# COMMUNICATION.net
KiCad netlist of a schematic drawn in Altium Designer
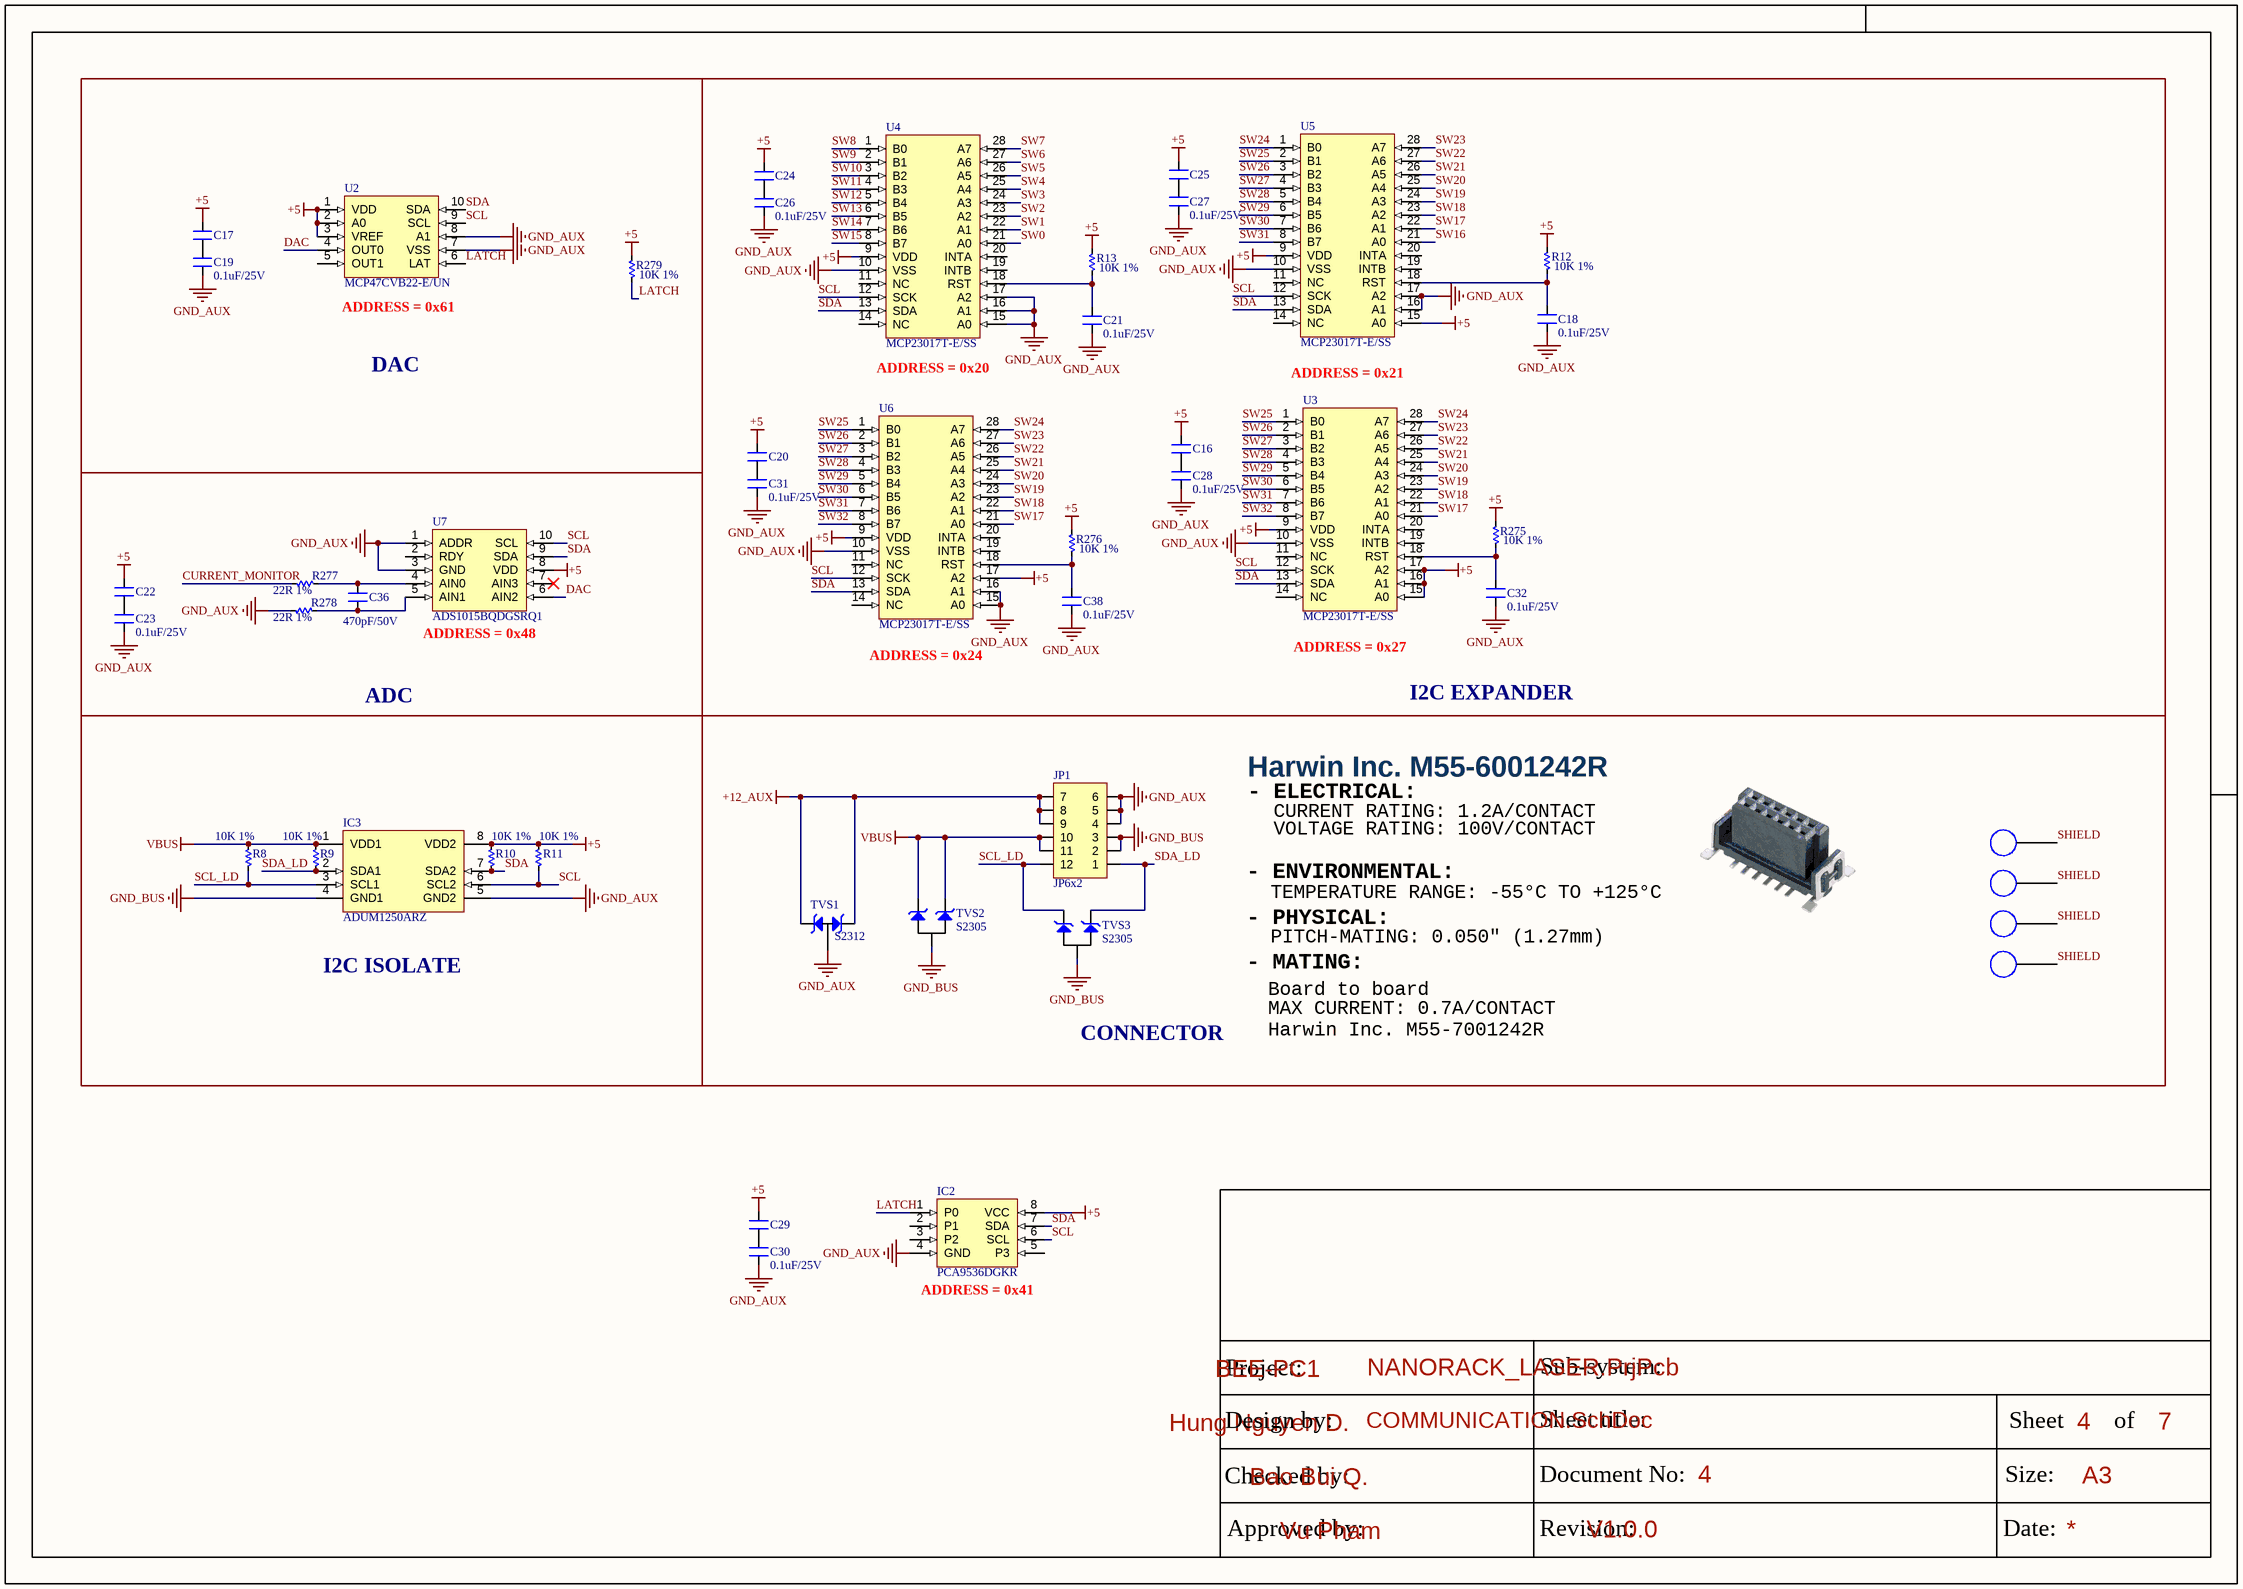
[diagram p0: COMMUNICATION.SchDoc]

(export (version "E")
  (design (tool "Eeschema 10.0.6"))
  (components
    (comp (ref "C16")
      (value "0.1uF/25V")
      (footprint "SM-0603")
      (description "0603")
      (libsource (lib "Capacitors") (part "CM"))
    )
    (comp (ref "C17")
      (value "0.1uF/25V")
      (footprint "SM-0603")
      (description "0603")
      (libsource (lib "Capacitors") (part "CM"))
    )
    (comp (ref "C18")
      (value "0.1uF/25V")
      (footprint "SM-0603")
      (description "0603")
      (libsource (lib "Capacitors") (part "CM"))
    )
    (comp (ref "C19")
      (value "0.1uF/25V")
      (footprint "SM-0603")
      (description "0603")
      (libsource (lib "Capacitors") (part "CM"))
    )
    (comp (ref "C20")
      (value "0.1uF/25V")
      (footprint "SM-0603")
      (description "0603")
      (libsource (lib "Capacitors") (part "CM"))
    )
    (comp (ref "C21")
      (value "0.1uF/25V")
      (footprint "SM-0603")
      (description "0603")
      (libsource (lib "Capacitors") (part "CM"))
    )
    (comp (ref "C22")
      (value "0.1uF/25V")
      (footprint "SM-0603")
      (description "0603")
      (libsource (lib "Capacitors") (part "CM"))
    )
    (comp (ref "C23")
      (value "0.1uF/25V")
      (footprint "SM-0603")
      (description "0603")
      (libsource (lib "Capacitors") (part "CM"))
    )
    (comp (ref "C24")
      (value "0.1uF/25V")
      (footprint "SM-0603")
      (description "0603")
      (libsource (lib "Capacitors") (part "CM"))
    )
    (comp (ref "C25")
      (value "0.1uF/25V")
      (footprint "SM-0603")
      (description "0603")
      (libsource (lib "Capacitors") (part "CM"))
    )
    (comp (ref "C26")
      (value "0.1uF/25V")
      (footprint "SM-0603")
      (description "0603")
      (libsource (lib "Capacitors") (part "CM"))
    )
    (comp (ref "C27")
      (value "0.1uF/25V")
      (footprint "SM-0603")
      (description "0603")
      (libsource (lib "Capacitors") (part "CM"))
    )
    (comp (ref "C28")
      (value "0.1uF/25V")
      (footprint "SM-0603")
      (description "0603")
      (libsource (lib "Capacitors") (part "CM"))
    )
    (comp (ref "C29")
      (value "0.1uF/25V")
      (footprint "SM-0603")
      (description "0603")
      (libsource (lib "Capacitors") (part "CM"))
    )
    (comp (ref "C30")
      (value "0.1uF/25V")
      (footprint "SM-0603")
      (description "0603")
      (libsource (lib "Capacitors") (part "CM"))
    )
    (comp (ref "C31")
      (value "0.1uF/25V")
      (footprint "SM-0603")
      (description "0603")
      (libsource (lib "Capacitors") (part "CM"))
    )
    (comp (ref "C32")
      (value "0.1uF/25V")
      (footprint "SM-0603")
      (description "0603")
      (libsource (lib "Capacitors") (part "CM"))
    )
    (comp (ref "C36")
      (value "470pF/50V")
      (footprint "SM-0603")
      (description "0603")
      (libsource (lib "Capacitors") (part "CM"))
    )
    (comp (ref "C38")
      (value "0.1uF/25V")
      (footprint "SM-0603")
      (description "0603")
      (libsource (lib "Capacitors") (part "CM"))
    )
    (comp (ref "H1") (value "M3") (footprint "M3") (libsource (lib "Library") (part "M3")))
    (comp (ref "H2") (value "M3") (footprint "M3") (libsource (lib "Library") (part "M3")))
    (comp (ref "H3") (value "M3") (footprint "M3") (libsource (lib "Library") (part "M3")))
    (comp (ref "H4") (value "M3") (footprint "M3") (libsource (lib "Library") (part "M3")))
    (comp (ref "IC2") (value "PCA9536DGKR") (footprint "TSSOP8") (libsource (lib "Library") (part "PCA9536")))
    (comp (ref "IC3") (value "ADUM1250ARZ") (footprint "SO8") (libsource (lib "Library") (part "ADUM1250")))
    (comp (ref "JP1")
      (value "JP6x2")
      (footprint "M55-6001242R")
      (description "WR-PHD 2.54 mm Dual Socket Header")
      (fields
        (field (name "MANUFACTURER") "Würth Elektronik eiSos GmbH")
        (field (name "PARTNO") "61301221821")
        (field (name "CREATED BY") "Karrer Zheng")
      )
      (libsource (lib "Library") (part "JP6x2"))
    )
    (comp (ref "R8")
      (value "10K 1%")
      (footprint "RES-SMD-0603")
      (description "0603")
      (fields
        (field (name "MANUFACTURER") "Generic Components")
        (field (name "PUBLISHER") "Altium Hobart Technology Centre")
      )
      (libsource (lib "Library") (part "Res-SMD"))
    )
    (comp (ref "R9")
      (value "10K 1%")
      (footprint "RES-SMD-0603")
      (description "0603")
      (fields
        (field (name "MANUFACTURER") "Generic Components")
        (field (name "PUBLISHER") "Altium Hobart Technology Centre")
      )
      (libsource (lib "Library") (part "Res-SMD"))
    )
    (comp (ref "R10")
      (value "10K 1%")
      (footprint "RES-SMD-0603")
      (description "0603")
      (fields
        (field (name "MANUFACTURER") "Generic Components")
        (field (name "PUBLISHER") "Altium Hobart Technology Centre")
      )
      (libsource (lib "Library") (part "Res-SMD"))
    )
    (comp (ref "R11")
      (value "10K 1%")
      (footprint "RES-SMD-0603")
      (description "0603")
      (fields
        (field (name "MANUFACTURER") "Generic Components")
        (field (name "PUBLISHER") "Altium Hobart Technology Centre")
      )
      (libsource (lib "Library") (part "Res-SMD"))
    )
    (comp (ref "R12")
      (value "10K 1%")
      (footprint "RES-SMD-0603")
      (description "0603")
      (fields
        (field (name "MANUFACTURER") "Generic Components")
        (field (name "PUBLISHER") "Altium Hobart Technology Centre")
      )
      (libsource (lib "Library") (part "Res-SMD"))
    )
    (comp (ref "R13")
      (value "10K 1%")
      (footprint "RES-SMD-0603")
      (description "0603")
      (fields
        (field (name "MANUFACTURER") "Generic Components")
        (field (name "PUBLISHER") "Altium Hobart Technology Centre")
      )
      (libsource (lib "Library") (part "Res-SMD"))
    )
    (comp (ref "R275")
      (value "10K 1%")
      (footprint "RES-SMD-0603")
      (description "0603")
      (fields
        (field (name "MANUFACTURER") "Generic Components")
        (field (name "PUBLISHER") "Altium Hobart Technology Centre")
      )
      (libsource (lib "Library") (part "Res-SMD"))
    )
    (comp (ref "R276")
      (value "10K 1%")
      (footprint "RES-SMD-0603")
      (description "0603")
      (fields
        (field (name "MANUFACTURER") "Generic Components")
        (field (name "PUBLISHER") "Altium Hobart Technology Centre")
      )
      (libsource (lib "Library") (part "Res-SMD"))
    )
    (comp (ref "R277")
      (value "22R 1%")
      (footprint "RES-SMD-0603")
      (description "0603")
      (fields
        (field (name "MANUFACTURER") "Generic Components")
        (field (name "PUBLISHER") "Altium Hobart Technology Centre")
      )
      (libsource (lib "Library") (part "Res-SMD"))
    )
    (comp (ref "R278")
      (value "22R 1%")
      (footprint "RES-SMD-0603")
      (description "0603")
      (fields
        (field (name "MANUFACTURER") "Generic Components")
        (field (name "PUBLISHER") "Altium Hobart Technology Centre")
      )
      (libsource (lib "Library") (part "Res-SMD"))
    )
    (comp (ref "R279")
      (value "10K 1%")
      (footprint "RES-SMD-0603")
      (description "0603")
      (fields
        (field (name "MANUFACTURER") "Generic Components")
        (field (name "PUBLISHER") "Altium Hobart Technology Centre")
      )
      (libsource (lib "Library") (part "Res-SMD"))
    )
    (comp (ref "TVS1")
      (value "S2312")
      (footprint "SOT23-123")
      (description "TVS DIODE 12VWM 19VC SOT23, P/N:  S2312")
      (libsource (lib "Library") (part "S2315"))
    )
    (comp (ref "TVS2")
      (value "S2305")
      (footprint "SOT23-123")
      (description "TVS DIODE 5VWM 10.8VC SOT23, P/N:  \r\nS2305")
      (libsource (lib "Library") (part "S2303"))
    )
    (comp (ref "TVS3")
      (value "S2305")
      (footprint "SOT23-123")
      (description "TVS DIODE 5VWM 10.8VC SOT23, P/N:  \r\nS2305")
      (libsource (lib "Library") (part "S2303"))
    )
    (comp (ref "U2")
      (value "MCP47CVB22-E/UN")
      (footprint "MSOP10")
      (libsource (lib "Library") (part "MCP47CVB22"))
    )
    (comp (ref "U3")
      (value "MCP23017T-E/SS")
      (footprint "SSOP28")
      (libsource (lib "Library") (part "MCP23017"))
    )
    (comp (ref "U4")
      (value "MCP23017T-E/SS")
      (footprint "SSOP28")
      (libsource (lib "Library") (part "MCP23017"))
    )
    (comp (ref "U5")
      (value "MCP23017T-E/SS")
      (footprint "SSOP28")
      (libsource (lib "Library") (part "MCP23017"))
    )
    (comp (ref "U6")
      (value "MCP23017T-E/SS")
      (footprint "SSOP28")
      (libsource (lib "Library") (part "MCP23017"))
    )
    (comp (ref "U7")
      (value "ADS1015BQDGSRQ1")
      (footprint "VSSOP10")
      (libsource (lib "Library") (part "ADS1015"))
    )
  )
  (nets
    (net (code "1") (name "+5") (class "Default")
      (node (ref "C16") (pin "2") (pinfunction "2_2") (pintype "passive"))
      (node (ref "C17") (pin "2") (pinfunction "2_2") (pintype "passive"))
      (node (ref "C20") (pin "2") (pinfunction "2_2") (pintype "passive"))
      (node (ref "C22") (pin "2") (pinfunction "2_2") (pintype "passive"))
      (node (ref "C24") (pin "2") (pinfunction "2_2") (pintype "passive"))
      (node (ref "C25") (pin "2") (pinfunction "2_2") (pintype "passive"))
      (node (ref "C29") (pin "2") (pinfunction "2_2") (pintype "passive"))
      (node (ref "IC2") (pin "8") (pinfunction "VCC_8") (pintype "input"))
      (node (ref "IC3") (pin "8") (pinfunction "VDD2_8") (pintype "power_in"))
      (node (ref "R10") (pin "2") (pinfunction "2_2") (pintype "passive"))
      (node (ref "R11") (pin "2") (pinfunction "2_2") (pintype "passive"))
      (node (ref "R12") (pin "2") (pinfunction "2_2") (pintype "passive"))
      (node (ref "R13") (pin "2") (pinfunction "2_2") (pintype "passive"))
      (node (ref "R275") (pin "2") (pinfunction "2_2") (pintype "passive"))
      (node (ref "R276") (pin "2") (pinfunction "2_2") (pintype "passive"))
      (node (ref "R279") (pin "2") (pinfunction "2_2") (pintype "passive"))
      (node (ref "U2") (pin "1") (pinfunction "VDD_1") (pintype "input"))
      (node (ref "U2") (pin "2") (pinfunction "A0_2") (pintype "input"))
      (node (ref "U2") (pin "3") (pinfunction "VREF_3") (pintype "input"))
      (node (ref "U3") (pin "15") (pinfunction "A0_15") (pintype "input"))
      (node (ref "U3") (pin "16") (pinfunction "A1_16") (pintype "input"))
      (node (ref "U3") (pin "17") (pinfunction "A2_17") (pintype "input"))
      (node (ref "U3") (pin "9") (pinfunction "VDD_9") (pintype "input"))
      (node (ref "U4") (pin "9") (pinfunction "VDD_9") (pintype "input"))
      (node (ref "U5") (pin "15") (pinfunction "A0_15") (pintype "input"))
      (node (ref "U5") (pin "9") (pinfunction "VDD_9") (pintype "input"))
      (node (ref "U6") (pin "17") (pinfunction "A2_17") (pintype "input"))
      (node (ref "U6") (pin "9") (pinfunction "VDD_9") (pintype "input"))
      (node (ref "U7") (pin "8") (pinfunction "VDD_8") (pintype "input"))
    )
    (net (code "2") (name "+12_AUX") (class "Default")
      (node (ref "JP1") (pin "7") (pinfunction "7_7") (pintype "passive"))
      (node (ref "JP1") (pin "8") (pinfunction "8_8") (pintype "passive"))
      (node (ref "JP1") (pin "9") (pinfunction "9_9") (pintype "passive"))
      (node (ref "TVS1") (pin "1") (pintype "passive"))
      (node (ref "TVS1") (pin "3") (pintype "passive"))
    )
    (net (code "3") (name "/CURRENT_MONITOR") (class "Default")
      (node (ref "R277") (pin "2") (pinfunction "2_2") (pintype "passive"))
    )
    (net (code "4") (name "/DAC") (class "Default")
      (node (ref "U2") (pin "4") (pinfunction "OUT0_4") (pintype "input"))
      (node (ref "U7") (pin "6") (pinfunction "AIN2_6") (pintype "input"))
    )
    (net (code "5") (name "/LATCH") (class "Default")
      (node (ref "IC2") (pin "1") (pinfunction "P0_1") (pintype "input"))
      (node (ref "R279") (pin "1") (pinfunction "1_1") (pintype "passive"))
      (node (ref "U2") (pin "6") (pinfunction "LAT_6") (pintype "input"))
    )
    (net (code "6") (name "/SCL") (class "Default")
      (node (ref "IC2") (pin "6") (pinfunction "SCL_6") (pintype "input"))
      (node (ref "IC3") (pin "6") (pinfunction "SCL2_6") (pintype "input"))
      (node (ref "R11") (pin "1") (pinfunction "1_1") (pintype "passive"))
      (node (ref "U2") (pin "9") (pinfunction "SCL_9") (pintype "input"))
      (node (ref "U3") (pin "12") (pinfunction "SCK_12") (pintype "input"))
      (node (ref "U4") (pin "12") (pinfunction "SCK_12") (pintype "input"))
      (node (ref "U5") (pin "12") (pinfunction "SCK_12") (pintype "input"))
      (node (ref "U6") (pin "12") (pinfunction "SCK_12") (pintype "input"))
      (node (ref "U7") (pin "10") (pinfunction "SCL_10") (pintype "input"))
    )
    (net (code "7") (name "/SCL_LD") (class "Default")
      (node (ref "IC3") (pin "3") (pinfunction "SCL1_3") (pintype "input"))
      (node (ref "JP1") (pin "12") (pinfunction "12_12") (pintype "passive"))
      (node (ref "R8") (pin "1") (pinfunction "1_1") (pintype "passive"))
      (node (ref "TVS3") (pin "3") (pintype "passive"))
    )
    (net (code "8") (name "/SDA") (class "Default")
      (node (ref "IC2") (pin "7") (pinfunction "SDA_7") (pintype "input"))
      (node (ref "IC3") (pin "7") (pinfunction "SDA2_7") (pintype "input"))
      (node (ref "R10") (pin "1") (pinfunction "1_1") (pintype "passive"))
      (node (ref "U2") (pin "10") (pinfunction "SDA_10") (pintype "input"))
      (node (ref "U3") (pin "13") (pinfunction "SDA_13") (pintype "input"))
      (node (ref "U4") (pin "13") (pinfunction "SDA_13") (pintype "input"))
      (node (ref "U5") (pin "13") (pinfunction "SDA_13") (pintype "input"))
      (node (ref "U6") (pin "13") (pinfunction "SDA_13") (pintype "input"))
      (node (ref "U7") (pin "9") (pinfunction "SDA_9") (pintype "input"))
    )
    (net (code "9") (name "/SDA_LD") (class "Default")
      (node (ref "IC3") (pin "2") (pinfunction "SDA1_2") (pintype "input"))
      (node (ref "JP1") (pin "1") (pinfunction "1_1") (pintype "passive"))
      (node (ref "R9") (pin "1") (pinfunction "1_1") (pintype "passive"))
      (node (ref "TVS3") (pin "1") (pintype "passive"))
    )
    (net (code "10") (name "/SHIELD") (class "Default")
      (node (ref "H1") (pin "1") (pinfunction "76_1") (pintype "passive"))
      (node (ref "H2") (pin "1") (pinfunction "76_1") (pintype "passive"))
      (node (ref "H3") (pin "1") (pinfunction "76_1") (pintype "passive"))
      (node (ref "H4") (pin "1") (pinfunction "76_1") (pintype "passive"))
    )
    (net (code "11") (name "/SW0") (class "Default")
      (node (ref "U4") (pin "21") (pinfunction "A0_21") (pintype "input"))
    )
    (net (code "12") (name "/SW1") (class "Default")
      (node (ref "U4") (pin "22") (pinfunction "A1_22") (pintype "input"))
    )
    (net (code "13") (name "/SW2") (class "Default")
      (node (ref "U4") (pin "23") (pinfunction "A2_23") (pintype "input"))
    )
    (net (code "14") (name "/SW3") (class "Default")
      (node (ref "U4") (pin "24") (pinfunction "A3_24") (pintype "input"))
    )
    (net (code "15") (name "/SW4") (class "Default")
      (node (ref "U4") (pin "25") (pinfunction "A4_25") (pintype "input"))
    )
    (net (code "16") (name "/SW5") (class "Default")
      (node (ref "U4") (pin "26") (pinfunction "A5_26") (pintype "input"))
    )
    (net (code "17") (name "/SW6") (class "Default")
      (node (ref "U4") (pin "27") (pinfunction "A6_27") (pintype "input"))
    )
    (net (code "18") (name "/SW7") (class "Default")
      (node (ref "U4") (pin "28") (pinfunction "A7_28") (pintype "input"))
    )
    (net (code "19") (name "/SW8") (class "Default")
      (node (ref "U4") (pin "1") (pinfunction "B0_1") (pintype "input"))
    )
    (net (code "20") (name "/SW9") (class "Default")
      (node (ref "U4") (pin "2") (pinfunction "B1_2") (pintype "input"))
    )
    (net (code "21") (name "/SW10") (class "Default")
      (node (ref "U4") (pin "3") (pinfunction "B2_3") (pintype "input"))
    )
    (net (code "22") (name "/SW11") (class "Default")
      (node (ref "U4") (pin "4") (pinfunction "B3_4") (pintype "input"))
    )
    (net (code "23") (name "/SW12") (class "Default")
      (node (ref "U4") (pin "5") (pinfunction "B4_5") (pintype "input"))
    )
    (net (code "24") (name "/SW13") (class "Default")
      (node (ref "U4") (pin "6") (pinfunction "B5_6") (pintype "input"))
    )
    (net (code "25") (name "/SW14") (class "Default")
      (node (ref "U4") (pin "7") (pinfunction "B6_7") (pintype "input"))
    )
    (net (code "26") (name "/SW15") (class "Default")
      (node (ref "U4") (pin "8") (pinfunction "B7_8") (pintype "input"))
    )
    (net (code "27") (name "/SW16") (class "Default")
      (node (ref "U5") (pin "21") (pinfunction "A0_21") (pintype "input"))
    )
    (net (code "28") (name "/SW17") (class "Default")
      (node (ref "U3") (pin "21") (pinfunction "A0_21") (pintype "input"))
      (node (ref "U5") (pin "22") (pinfunction "A1_22") (pintype "input"))
      (node (ref "U6") (pin "21") (pinfunction "A0_21") (pintype "input"))
    )
    (net (code "29") (name "/SW18") (class "Default")
      (node (ref "U3") (pin "22") (pinfunction "A1_22") (pintype "input"))
      (node (ref "U5") (pin "23") (pinfunction "A2_23") (pintype "input"))
      (node (ref "U6") (pin "22") (pinfunction "A1_22") (pintype "input"))
    )
    (net (code "30") (name "/SW19") (class "Default")
      (node (ref "U3") (pin "23") (pinfunction "A2_23") (pintype "input"))
      (node (ref "U5") (pin "24") (pinfunction "A3_24") (pintype "input"))
      (node (ref "U6") (pin "23") (pinfunction "A2_23") (pintype "input"))
    )
    (net (code "31") (name "/SW20") (class "Default")
      (node (ref "U3") (pin "24") (pinfunction "A3_24") (pintype "input"))
      (node (ref "U5") (pin "25") (pinfunction "A4_25") (pintype "input"))
      (node (ref "U6") (pin "24") (pinfunction "A3_24") (pintype "input"))
    )
    (net (code "32") (name "/SW21") (class "Default")
      (node (ref "U3") (pin "25") (pinfunction "A4_25") (pintype "input"))
      (node (ref "U5") (pin "26") (pinfunction "A5_26") (pintype "input"))
      (node (ref "U6") (pin "25") (pinfunction "A4_25") (pintype "input"))
    )
    (net (code "33") (name "/SW22") (class "Default")
      (node (ref "U3") (pin "26") (pinfunction "A5_26") (pintype "input"))
      (node (ref "U5") (pin "27") (pinfunction "A6_27") (pintype "input"))
      (node (ref "U6") (pin "26") (pinfunction "A5_26") (pintype "input"))
    )
    (net (code "34") (name "/SW23") (class "Default")
      (node (ref "U3") (pin "27") (pinfunction "A6_27") (pintype "input"))
      (node (ref "U5") (pin "28") (pinfunction "A7_28") (pintype "input"))
      (node (ref "U6") (pin "27") (pinfunction "A6_27") (pintype "input"))
    )
    (net (code "35") (name "/SW24") (class "Default")
      (node (ref "U3") (pin "28") (pinfunction "A7_28") (pintype "input"))
      (node (ref "U5") (pin "1") (pinfunction "B0_1") (pintype "input"))
      (node (ref "U6") (pin "28") (pinfunction "A7_28") (pintype "input"))
    )
    (net (code "36") (name "/SW25") (class "Default")
      (node (ref "U3") (pin "1") (pinfunction "B0_1") (pintype "input"))
      (node (ref "U5") (pin "2") (pinfunction "B1_2") (pintype "input"))
      (node (ref "U6") (pin "1") (pinfunction "B0_1") (pintype "input"))
    )
    (net (code "37") (name "/SW26") (class "Default")
      (node (ref "U3") (pin "2") (pinfunction "B1_2") (pintype "input"))
      (node (ref "U5") (pin "3") (pinfunction "B2_3") (pintype "input"))
      (node (ref "U6") (pin "2") (pinfunction "B1_2") (pintype "input"))
    )
    (net (code "38") (name "/SW27") (class "Default")
      (node (ref "U3") (pin "3") (pinfunction "B2_3") (pintype "input"))
      (node (ref "U5") (pin "4") (pinfunction "B3_4") (pintype "input"))
      (node (ref "U6") (pin "3") (pinfunction "B2_3") (pintype "input"))
    )
    (net (code "39") (name "/SW28") (class "Default")
      (node (ref "U3") (pin "4") (pinfunction "B3_4") (pintype "input"))
      (node (ref "U5") (pin "5") (pinfunction "B4_5") (pintype "input"))
      (node (ref "U6") (pin "4") (pinfunction "B3_4") (pintype "input"))
    )
    (net (code "40") (name "/SW29") (class "Default")
      (node (ref "U3") (pin "5") (pinfunction "B4_5") (pintype "input"))
      (node (ref "U5") (pin "6") (pinfunction "B5_6") (pintype "input"))
      (node (ref "U6") (pin "5") (pinfunction "B4_5") (pintype "input"))
    )
    (net (code "41") (name "/SW30") (class "Default")
      (node (ref "U3") (pin "6") (pinfunction "B5_6") (pintype "input"))
      (node (ref "U5") (pin "7") (pinfunction "B6_7") (pintype "input"))
      (node (ref "U6") (pin "6") (pinfunction "B5_6") (pintype "input"))
    )
    (net (code "42") (name "/SW31") (class "Default")
      (node (ref "U3") (pin "7") (pinfunction "B6_7") (pintype "input"))
      (node (ref "U5") (pin "8") (pinfunction "B7_8") (pintype "input"))
      (node (ref "U6") (pin "7") (pinfunction "B6_7") (pintype "input"))
    )
    (net (code "43") (name "/SW32") (class "Default")
      (node (ref "U3") (pin "8") (pinfunction "B7_8") (pintype "input"))
      (node (ref "U6") (pin "8") (pinfunction "B7_8") (pintype "input"))
    )
    (net (code "44") (name "GND_AUX") (class "Default")
      (node (ref "C18") (pin "1") (pinfunction "1_1") (pintype "passive"))
      (node (ref "C19") (pin "1") (pinfunction "1_1") (pintype "passive"))
      (node (ref "C21") (pin "1") (pinfunction "1_1") (pintype "passive"))
      (node (ref "C23") (pin "1") (pinfunction "1_1") (pintype "passive"))
      (node (ref "C26") (pin "1") (pinfunction "1_1") (pintype "passive"))
      (node (ref "C27") (pin "1") (pinfunction "1_1") (pintype "passive"))
      (node (ref "C28") (pin "1") (pinfunction "1_1") (pintype "passive"))
      (node (ref "C30") (pin "1") (pinfunction "1_1") (pintype "passive"))
      (node (ref "C31") (pin "1") (pinfunction "1_1") (pintype "passive"))
      (node (ref "C32") (pin "1") (pinfunction "1_1") (pintype "passive"))
      (node (ref "C38") (pin "1") (pinfunction "1_1") (pintype "passive"))
      (node (ref "IC2") (pin "4") (pinfunction "GND_4") (pintype "input"))
      (node (ref "IC3") (pin "5") (pinfunction "GND2_5") (pintype "power_in"))
      (node (ref "JP1") (pin "4") (pinfunction "4_4") (pintype "passive"))
      (node (ref "JP1") (pin "5") (pinfunction "5_5") (pintype "passive"))
      (node (ref "JP1") (pin "6") (pinfunction "6_6") (pintype "passive"))
      (node (ref "R278") (pin "2") (pinfunction "2_2") (pintype "passive"))
      (node (ref "TVS1") (pin "2") (pintype "passive"))
      (node (ref "U2") (pin "7") (pinfunction "VSS_7") (pintype "input"))
      (node (ref "U2") (pin "8") (pinfunction "A1_8") (pintype "input"))
      (node (ref "U3") (pin "10") (pinfunction "VSS_10") (pintype "input"))
      (node (ref "U4") (pin "10") (pinfunction "VSS_10") (pintype "input"))
      (node (ref "U4") (pin "15") (pinfunction "A0_15") (pintype "input"))
      (node (ref "U4") (pin "16") (pinfunction "A1_16") (pintype "input"))
      (node (ref "U4") (pin "17") (pinfunction "A2_17") (pintype "input"))
      (node (ref "U5") (pin "10") (pinfunction "VSS_10") (pintype "input"))
      (node (ref "U5") (pin "16") (pinfunction "A1_16") (pintype "input"))
      (node (ref "U5") (pin "17") (pinfunction "A2_17") (pintype "input"))
      (node (ref "U6") (pin "10") (pinfunction "VSS_10") (pintype "input"))
      (node (ref "U6") (pin "15") (pinfunction "A0_15") (pintype "input"))
      (node (ref "U6") (pin "16") (pinfunction "A1_16") (pintype "input"))
      (node (ref "U7") (pin "1") (pinfunction "ADDR_1") (pintype "input"))
      (node (ref "U7") (pin "3") (pinfunction "GND_3") (pintype "input"))
    )
    (net (code "45") (name "GND_BUS") (class "Default")
      (node (ref "IC3") (pin "4") (pinfunction "GND1_4") (pintype "power_in"))
      (node (ref "JP1") (pin "2") (pinfunction "2_2") (pintype "passive"))
      (node (ref "JP1") (pin "3") (pinfunction "3_3") (pintype "passive"))
      (node (ref "TVS2") (pin "2") (pintype "passive"))
      (node (ref "TVS3") (pin "2") (pintype "passive"))
    )
    (net (code "46") (name "Net-(C16-Pad1)") (class "Default")
      (node (ref "C16") (pin "1") (pinfunction "1_1") (pintype "passive"))
      (node (ref "C28") (pin "2") (pinfunction "2_2") (pintype "passive"))
    )
    (net (code "47") (name "Net-(C17-Pad1)") (class "Default")
      (node (ref "C17") (pin "1") (pinfunction "1_1") (pintype "passive"))
      (node (ref "C19") (pin "2") (pinfunction "2_2") (pintype "passive"))
    )
    (net (code "48") (name "Net-(C20-Pad1)") (class "Default")
      (node (ref "C20") (pin "1") (pinfunction "1_1") (pintype "passive"))
      (node (ref "C31") (pin "2") (pinfunction "2_2") (pintype "passive"))
    )
    (net (code "49") (name "Net-(C22-Pad1)") (class "Default")
      (node (ref "C22") (pin "1") (pinfunction "1_1") (pintype "passive"))
      (node (ref "C23") (pin "2") (pinfunction "2_2") (pintype "passive"))
    )
    (net (code "50") (name "Net-(C24-Pad1)") (class "Default")
      (node (ref "C24") (pin "1") (pinfunction "1_1") (pintype "passive"))
      (node (ref "C26") (pin "2") (pinfunction "2_2") (pintype "passive"))
    )
    (net (code "51") (name "Net-(C25-Pad1)") (class "Default")
      (node (ref "C25") (pin "1") (pinfunction "1_1") (pintype "passive"))
      (node (ref "C27") (pin "2") (pinfunction "2_2") (pintype "passive"))
    )
    (net (code "52") (name "Net-(C29-Pad1)") (class "Default")
      (node (ref "C29") (pin "1") (pinfunction "1_1") (pintype "passive"))
      (node (ref "C30") (pin "2") (pinfunction "2_2") (pintype "passive"))
    )
    (net (code "53") (name "Net-(U3-RST)") (class "Default")
      (node (ref "C32") (pin "2") (pinfunction "2_2") (pintype "passive"))
      (node (ref "R275") (pin "1") (pinfunction "1_1") (pintype "passive"))
      (node (ref "U3") (pin "18") (pinfunction "RST_18") (pintype "input"))
    )
    (net (code "54") (name "Net-(U4-RST)") (class "Default")
      (node (ref "C21") (pin "2") (pinfunction "2_2") (pintype "passive"))
      (node (ref "R13") (pin "1") (pinfunction "1_1") (pintype "passive"))
      (node (ref "U4") (pin "18") (pinfunction "RST_18") (pintype "input"))
    )
    (net (code "55") (name "Net-(U5-RST)") (class "Default")
      (node (ref "C18") (pin "2") (pinfunction "2_2") (pintype "passive"))
      (node (ref "R12") (pin "1") (pinfunction "1_1") (pintype "passive"))
      (node (ref "U5") (pin "18") (pinfunction "RST_18") (pintype "input"))
    )
    (net (code "56") (name "Net-(U6-RST)") (class "Default")
      (node (ref "C38") (pin "2") (pinfunction "2_2") (pintype "passive"))
      (node (ref "R276") (pin "1") (pinfunction "1_1") (pintype "passive"))
      (node (ref "U6") (pin "18") (pinfunction "RST_18") (pintype "input"))
    )
    (net (code "57") (name "Net-(U7-AIN0)") (class "Default")
      (node (ref "C36") (pin "2") (pinfunction "2_2") (pintype "passive"))
      (node (ref "R277") (pin "1") (pinfunction "1_1") (pintype "passive"))
      (node (ref "U7") (pin "4") (pinfunction "AIN0_4") (pintype "input"))
    )
    (net (code "58") (name "Net-(U7-AIN1)") (class "Default")
      (node (ref "C36") (pin "1") (pinfunction "1_1") (pintype "passive"))
      (node (ref "R278") (pin "1") (pinfunction "1_1") (pintype "passive"))
      (node (ref "U7") (pin "5") (pinfunction "AIN1_5") (pintype "input"))
    )
    (net (code "59") (name "VBUS") (class "Default")
      (node (ref "IC3") (pin "1") (pinfunction "VDD1_1") (pintype "power_in"))
      (node (ref "JP1") (pin "10") (pinfunction "10_10") (pintype "passive"))
      (node (ref "JP1") (pin "11") (pinfunction "11_11") (pintype "passive"))
      (node (ref "R8") (pin "2") (pinfunction "2_2") (pintype "passive"))
      (node (ref "R9") (pin "2") (pinfunction "2_2") (pintype "passive"))
      (node (ref "TVS2") (pin "1") (pintype "passive"))
      (node (ref "TVS2") (pin "3") (pintype "passive"))
    )
    (net (code "60") (name "unconnected-(IC2-P1-Pad2)") (class "Default")
      (node (ref "IC2") (pin "2") (pinfunction "P1_2") (pintype "input"))
    )
    (net (code "61") (name "unconnected-(IC2-P2-Pad3)") (class "Default")
      (node (ref "IC2") (pin "3") (pinfunction "P2_3") (pintype "input"))
    )
    (net (code "62") (name "unconnected-(IC2-P3-Pad5)") (class "Default")
      (node (ref "IC2") (pin "5") (pinfunction "P3_5") (pintype "input"))
    )
    (net (code "63") (name "unconnected-(U2-OUT1-Pad5)") (class "Default")
      (node (ref "U2") (pin "5") (pinfunction "OUT1_5") (pintype "input"))
    )
    (net (code "64") (name "unconnected-(U3-INTA-Pad20)") (class "Default")
      (node (ref "U3") (pin "20") (pinfunction "INTA_20") (pintype "input"))
    )
    (net (code "65") (name "unconnected-(U3-INTB-Pad19)") (class "Default")
      (node (ref "U3") (pin "19") (pinfunction "INTB_19") (pintype "input"))
    )
    (net (code "66") (name "unconnected-(U3-NC-Pad11)") (class "Default")
      (node (ref "U3") (pin "11") (pinfunction "NC_11") (pintype "input"))
    )
    (net (code "67") (name "unconnected-(U3-NC-Pad14)") (class "Default")
      (node (ref "U3") (pin "14") (pinfunction "NC_14") (pintype "input"))
    )
    (net (code "68") (name "unconnected-(U4-INTA-Pad20)") (class "Default")
      (node (ref "U4") (pin "20") (pinfunction "INTA_20") (pintype "input"))
    )
    (net (code "69") (name "unconnected-(U4-INTB-Pad19)") (class "Default")
      (node (ref "U4") (pin "19") (pinfunction "INTB_19") (pintype "input"))
    )
    (net (code "70") (name "unconnected-(U4-NC-Pad11)") (class "Default")
      (node (ref "U4") (pin "11") (pinfunction "NC_11") (pintype "input"))
    )
    (net (code "71") (name "unconnected-(U4-NC-Pad14)") (class "Default")
      (node (ref "U4") (pin "14") (pinfunction "NC_14") (pintype "input"))
    )
    (net (code "72") (name "unconnected-(U5-INTA-Pad20)") (class "Default")
      (node (ref "U5") (pin "20") (pinfunction "INTA_20") (pintype "input"))
    )
    (net (code "73") (name "unconnected-(U5-INTB-Pad19)") (class "Default")
      (node (ref "U5") (pin "19") (pinfunction "INTB_19") (pintype "input"))
    )
    (net (code "74") (name "unconnected-(U5-NC-Pad11)") (class "Default")
      (node (ref "U5") (pin "11") (pinfunction "NC_11") (pintype "input"))
    )
    (net (code "75") (name "unconnected-(U5-NC-Pad14)") (class "Default")
      (node (ref "U5") (pin "14") (pinfunction "NC_14") (pintype "input"))
    )
    (net (code "76") (name "unconnected-(U6-INTA-Pad20)") (class "Default")
      (node (ref "U6") (pin "20") (pinfunction "INTA_20") (pintype "input"))
    )
    (net (code "77") (name "unconnected-(U6-INTB-Pad19)") (class "Default")
      (node (ref "U6") (pin "19") (pinfunction "INTB_19") (pintype "input"))
    )
    (net (code "78") (name "unconnected-(U6-NC-Pad11)") (class "Default")
      (node (ref "U6") (pin "11") (pinfunction "NC_11") (pintype "input"))
    )
    (net (code "79") (name "unconnected-(U6-NC-Pad14)") (class "Default")
      (node (ref "U6") (pin "14") (pinfunction "NC_14") (pintype "input"))
    )
    (net (code "80") (name "unconnected-(U7-AIN3-Pad7)") (class "Default")
      (node (ref "U7") (pin "7") (pinfunction "AIN3_7") (pintype "input+no_connect"))
    )
    (net (code "81") (name "unconnected-(U7-RDY-Pad2)") (class "Default")
      (node (ref "U7") (pin "2") (pinfunction "RDY_2") (pintype "input"))
    )
  )
)
